# usbuddy.net
KiCad netlist of a schematic drawn in EAGLE
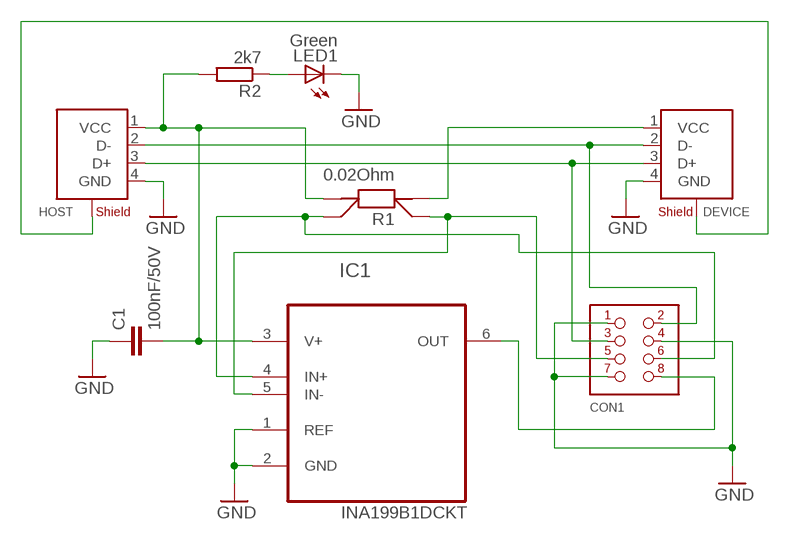
[diagram p0: schematic, sheet 1]

(export (version "E")
  (design (tool "Eeschema 10.0.6"))
  (components
    (comp (ref "C1")
      (value "100nF/50V")
      (footprint "eagle-import:C0603K")
      (libsource (lib "eagle-import") (part "C-EUC0603K"))
    )
    (comp (ref "CON1")
      (value "PINHEAD-02X04-SMT-2.54")
      (footprint "eagle-import:2X04-SMT-PINHEAD")
      (libsource (lib "eagle-import") (part "PINHEAD-02X04-SMT-2.54"))
    )
    (comp (ref "DEVICE")
      (value "USB-A-SMT")
      (footprint "eagle-import:USB-A-SMT-UBA-4R-S14HD-4S")
      (libsource (lib "eagle-import") (part "USB-A-SMT"))
    )
    (comp (ref "HOST")
      (value "USB-B-SMT")
      (footprint "eagle-import:USB-B-SMT")
      (libsource (lib "eagle-import") (part "USB-B-SMT"))
    )
    (comp (ref "IC1")
      (value "INA199A2DCKR")
      (footprint "eagle-import:SOT65P210X110-6N")
      (fields (field (name "MPN") "INA199A2DCKR") (field (name "MPN_1") "INA199B1DCKT"))
      (libsource (lib "eagle-import") (part "INA199A2DCKR"))
    )
    (comp (ref "LED1")
      (value "Green")
      (footprint "eagle-import:CHIP-LED0603")
      (libsource (lib "eagle-import") (part "LEDCHIP-LED0603"))
    )
    (comp (ref "R1")
      (value "0.02Ohm")
      (footprint "eagle-import:1206-4WIRE")
      (libsource (lib "eagle-import") (part "LVK12"))
    )
    (comp (ref "R2")
      (value "2k7")
      (footprint "eagle-import:R1206")
      (libsource (lib "eagle-import") (part "R-EU_R1206"))
    )
  )
  (nets
    (net (code "1") (name "GND") (class "Default")
      (node (ref "C1") (pin "1") (pinfunction "1_1") (pintype "passive"))
      (node (ref "CON1") (pin "1") (pinfunction "1_1") (pintype "bidirectional"))
      (node (ref "CON1") (pin "4") (pinfunction "4_4") (pintype "bidirectional"))
      (node (ref "CON1") (pin "7") (pinfunction "7_7") (pintype "bidirectional"))
      (node (ref "DEVICE") (pin "4") (pinfunction "GND_4") (pintype "bidirectional"))
      (node (ref "HOST") (pin "4") (pinfunction "GND_4") (pintype "bidirectional"))
      (node (ref "IC1") (pin "1") (pinfunction "REF_1") (pintype "input"))
      (node (ref "IC1") (pin "2") (pinfunction "GND_2") (pintype "passive"))
      (node (ref "LED1") (pin "C") (pinfunction "C_C") (pintype "passive"))
    )
    (net (code "2") (name "Net-(DEVICE-D+)") (class "Default")
      (node (ref "CON1") (pin "3") (pinfunction "3_3") (pintype "bidirectional"))
      (node (ref "DEVICE") (pin "3") (pinfunction "D+_3") (pintype "bidirectional"))
      (node (ref "HOST") (pin "3") (pinfunction "D+_3") (pintype "bidirectional"))
    )
    (net (code "3") (name "Net-(DEVICE-D-)") (class "Default")
      (node (ref "CON1") (pin "2") (pinfunction "2_2") (pintype "bidirectional"))
      (node (ref "DEVICE") (pin "2") (pinfunction "D-_2") (pintype "bidirectional"))
      (node (ref "HOST") (pin "2") (pinfunction "D-_2") (pintype "bidirectional"))
    )
    (net (code "4") (name "Net-(DEVICE-SHIELD-PadS1)") (class "Default")
      (node (ref "DEVICE") (pin "S1") (pinfunction "SHIELD_S1") (pintype "bidirectional"))
      (node (ref "DEVICE") (pin "S2") (pinfunction "SHIELD_S2") (pintype "bidirectional"))
      (node (ref "DEVICE") (pin "S3") (pinfunction "SHIELD_S3") (pintype "bidirectional"))
      (node (ref "DEVICE") (pin "S4") (pinfunction "SHIELD_S4") (pintype "bidirectional"))
      (node (ref "HOST") (pin "S1") (pinfunction "SHIELD_S1") (pintype "bidirectional"))
      (node (ref "HOST") (pin "S2") (pinfunction "SHIELD_S2") (pintype "bidirectional"))
    )
    (net (code "5") (name "Net-(DEVICE-VCC)") (class "Default")
      (node (ref "DEVICE") (pin "1") (pinfunction "VCC_1") (pintype "bidirectional"))
      (node (ref "R1") (pin "I1") (pinfunction "I1_I1") (pintype "bidirectional"))
    )
    (net (code "6") (name "Net-(HOST-VCC)") (class "Default")
      (node (ref "C1") (pin "2") (pinfunction "2_2") (pintype "passive"))
      (node (ref "HOST") (pin "1") (pinfunction "VCC_1") (pintype "bidirectional"))
      (node (ref "IC1") (pin "3") (pinfunction "V+_3") (pintype "power_in"))
      (node (ref "R1") (pin "I2") (pinfunction "I2_I2") (pintype "bidirectional"))
      (node (ref "R2") (pin "2") (pinfunction "2_2") (pintype "passive"))
    )
    (net (code "7") (name "Net-(IC1-IN+)") (class "Default")
      (node (ref "CON1") (pin "6") (pinfunction "6_6") (pintype "bidirectional"))
      (node (ref "IC1") (pin "4") (pinfunction "IN+_4") (pintype "input"))
      (node (ref "R1") (pin "V2") (pinfunction "V2_V2") (pintype "bidirectional"))
    )
    (net (code "8") (name "Net-(IC1-IN-)") (class "Default")
      (node (ref "CON1") (pin "5") (pinfunction "5_5") (pintype "bidirectional"))
      (node (ref "IC1") (pin "5") (pinfunction "IN-_5") (pintype "input"))
      (node (ref "R1") (pin "V1") (pinfunction "V1_V1") (pintype "bidirectional"))
    )
    (net (code "9") (name "Net-(IC1-OUT)") (class "Default")
      (node (ref "CON1") (pin "8") (pinfunction "8_8") (pintype "bidirectional"))
      (node (ref "IC1") (pin "6") (pinfunction "OUT_6") (pintype "output"))
    )
    (net (code "10") (name "Net-(LED1-PadA)") (class "Default")
      (node (ref "LED1") (pin "A") (pinfunction "A_A") (pintype "passive"))
      (node (ref "R2") (pin "1") (pinfunction "1_1") (pintype "passive"))
    )
  )
)
